# PAGE15.net
KiCad netlist of a schematic drawn in Altium Designer
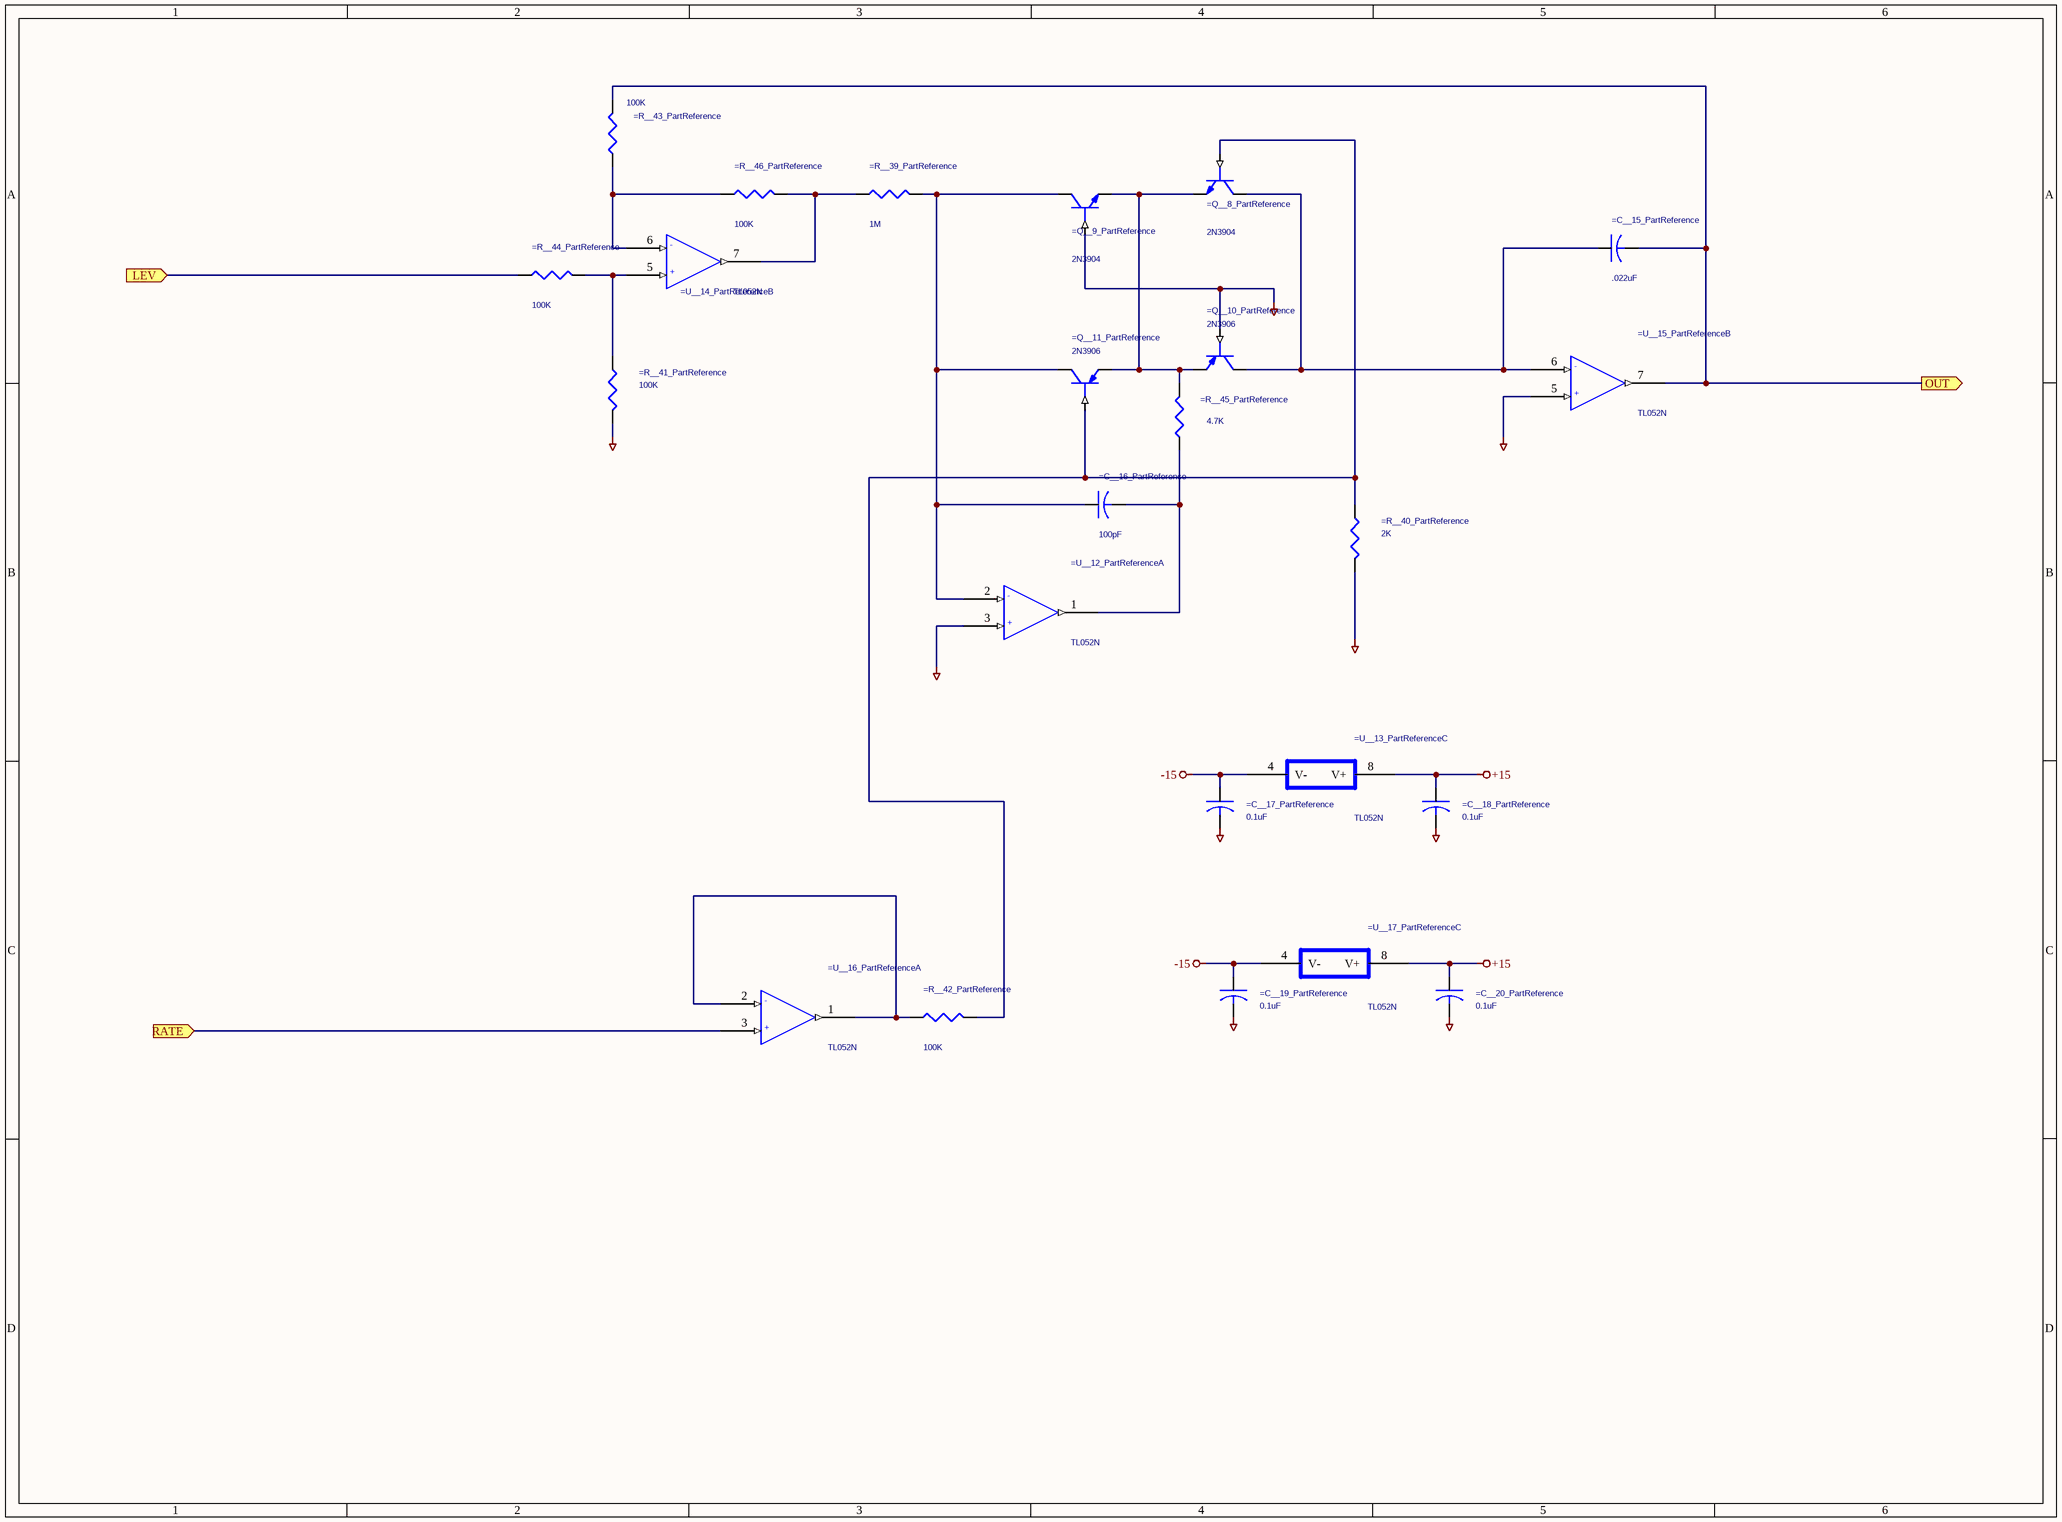
[diagram p0: PAGE15.SchDoc]

(export (version "E")
  (design (tool "Eeschema 10.0.6"))
  (components
    (comp (ref "=C__15_PartReference") (value ".022uF") (libsource (lib "*") (part "CAP_Dup1")))
    (comp (ref "=C__16_PartReference") (value "100pF") (libsource (lib "*") (part "CAP_Dup1")))
    (comp (ref "=C__17_PartReference") (value "0.1uF") (libsource (lib "*") (part "CAP_Dup1")))
    (comp (ref "=C__18_PartReference") (value "0.1uF") (libsource (lib "*") (part "CAP_Dup1")))
    (comp (ref "=C__19_PartReference") (value "0.1uF") (libsource (lib "*") (part "CAP_Dup1")))
    (comp (ref "=C__20_PartReference") (value "0.1uF") (libsource (lib "*") (part "CAP_Dup1")))
    (comp (ref "=Q__8_PartReference") (value "2N3904") (footprint "TO92") (libsource (lib "*") (part "NPN")))
    (comp (ref "=Q__9_PartReference") (value "2N3904") (footprint "TO92") (libsource (lib "*") (part "NPN")))
    (comp (ref "=Q__10_PartReference") (value "2N3906") (footprint "TO92") (libsource (lib "*") (part "PNP")))
    (comp (ref "=Q__11_PartReference") (value "2N3906") (footprint "TO92") (libsource (lib "*") (part "PNP")))
    (comp (ref "=R__39_PartReference") (value "1M") (libsource (lib "*") (part "R_Dup1")))
    (comp (ref "=R__40_PartReference") (value "2K") (libsource (lib "*") (part "R_Dup1")))
    (comp (ref "=R__41_PartReference") (value "100K") (libsource (lib "*") (part "R_Dup1")))
    (comp (ref "=R__42_PartReference") (value "100K") (libsource (lib "*") (part "R_Dup1")))
    (comp (ref "=R__43_PartReference") (value "100K") (libsource (lib "*") (part "R_Dup1")))
    (comp (ref "=R__44_PartReference") (value "100K") (libsource (lib "*") (part "R_Dup1")))
    (comp (ref "=R__45_PartReference") (value "4.7K") (libsource (lib "*") (part "R_Dup1")))
    (comp (ref "=R__46_PartReference") (value "100K") (libsource (lib "*") (part "R_Dup1")))
    (comp (ref "=U__12_PartReference")
      (value "TL052N")
      (footprint "DIP8")
      (libsource (lib "*") (part "TL052N"))
    )
    (comp (ref "=U__13_PartReference")
      (value "TL052N")
      (footprint "DIP8")
      (libsource (lib "*") (part "TL052N"))
    )
    (comp (ref "=U__14_PartReference")
      (value "TL052N")
      (footprint "DIP8")
      (libsource (lib "*") (part "TL052N"))
    )
    (comp (ref "=U__15_PartReference")
      (value "TL052N")
      (footprint "DIP8")
      (libsource (lib "*") (part "TL052N"))
    )
    (comp (ref "=U__16_PartReference")
      (value "TL052N")
      (footprint "DIP8")
      (libsource (lib "*") (part "TL052N"))
    )
    (comp (ref "=U__17_PartReference")
      (value "TL052N")
      (footprint "DIP8")
      (libsource (lib "*") (part "TL052N"))
    )
  )
  (nets
    (net (code "1") (name "+15") (class "Default")
      (node (ref "=C__18_PartReference") (pin "1") (pinfunction "1_1") (pintype "passive"))
      (node (ref "=C__20_PartReference") (pin "1") (pinfunction "1_1") (pintype "passive"))
      (node (ref "=U__13_PartReference") (pin "8") (pinfunction "V+_8") (pintype "passive"))
      (node (ref "=U__17_PartReference") (pin "8") (pinfunction "V+_8") (pintype "passive"))
    )
    (net (code "2") (name "-15") (class "Default")
      (node (ref "=C__17_PartReference") (pin "1") (pinfunction "1_1") (pintype "passive"))
      (node (ref "=C__19_PartReference") (pin "1") (pinfunction "1_1") (pintype "passive"))
      (node (ref "=U__13_PartReference") (pin "4") (pinfunction "V-_4") (pintype "passive"))
      (node (ref "=U__17_PartReference") (pin "4") (pinfunction "V-_4") (pintype "passive"))
    )
    (net (code "3") (name "/LEV") (class "Default")
      (node (ref "=R__44_PartReference") (pin "1") (pinfunction "1_1") (pintype "passive"))
    )
    (net (code "4") (name "/OUT") (class "Default")
      (node (ref "=C__15_PartReference") (pin "2") (pinfunction "2_2") (pintype "passive"))
      (node (ref "=R__43_PartReference") (pin "2") (pinfunction "2_2") (pintype "passive"))
      (node (ref "=U__15_PartReference") (pin "7") (pinfunction "OUT_7") (pintype "output"))
    )
    (net (code "5") (name "/RATE") (class "Default")
      (node (ref "=U__16_PartReference") (pin "3") (pinfunction "+_3") (pintype "input"))
    )
    (net (code "6") (name "AGND") (class "Default")
      (node (ref "=C__17_PartReference") (pin "2") (pinfunction "2_2") (pintype "passive"))
      (node (ref "=C__18_PartReference") (pin "2") (pinfunction "2_2") (pintype "passive"))
      (node (ref "=C__19_PartReference") (pin "2") (pinfunction "2_2") (pintype "passive"))
      (node (ref "=C__20_PartReference") (pin "2") (pinfunction "2_2") (pintype "passive"))
      (node (ref "=Q__10_PartReference") (pin "BASE") (pinfunction "BASE_BASE") (pintype "input"))
      (node (ref "=Q__9_PartReference") (pin "BASE") (pinfunction "BASE_BASE") (pintype "input"))
      (node (ref "=R__40_PartReference") (pin "2") (pinfunction "2_2") (pintype "passive"))
      (node (ref "=R__41_PartReference") (pin "2") (pinfunction "2_2") (pintype "passive"))
      (node (ref "=U__12_PartReference") (pin "3") (pinfunction "+_3") (pintype "input"))
      (node (ref "=U__15_PartReference") (pin "5") (pinfunction "+_5") (pintype "input"))
    )
    (net (code "7") (name "Net-(=Q__10_PartReference-PadEMITTER)") (class "Default")
      (node (ref "=Q__10_PartReference") (pin "EMITTER") (pinfunction "EMITTER_EMITTER") (pintype "passive"))
      (node (ref "=Q__11_PartReference") (pin "EMITTER") (pinfunction "EMITTER_EMITTER") (pintype "passive"))
      (node (ref "=Q__8_PartReference") (pin "EMITTER") (pinfunction "EMITTER_EMITTER") (pintype "passive"))
      (node (ref "=Q__9_PartReference") (pin "EMITTER") (pinfunction "EMITTER_EMITTER") (pintype "passive"))
      (node (ref "=R__45_PartReference") (pin "2") (pinfunction "2_2") (pintype "passive"))
    )
    (net (code "8") (name "Net-(=Q__11_PartReference-PadBASE)") (class "Default")
      (node (ref "=Q__11_PartReference") (pin "BASE") (pinfunction "BASE_BASE") (pintype "input"))
      (node (ref "=Q__8_PartReference") (pin "BASE") (pinfunction "BASE_BASE") (pintype "input"))
      (node (ref "=R__40_PartReference") (pin "1") (pinfunction "1_1") (pintype "passive"))
      (node (ref "=R__42_PartReference") (pin "2") (pinfunction "2_2") (pintype "passive"))
    )
    (net (code "9") (name "Net-(=U__12_PartReferenceA--)") (class "Default")
      (node (ref "=C__16_PartReference") (pin "1") (pinfunction "1_1") (pintype "passive"))
      (node (ref "=Q__11_PartReference") (pin "COLLECTOR") (pinfunction "COLLECTOR_COLLECTOR") (pintype "passive"))
      (node (ref "=Q__9_PartReference") (pin "COLLECTOR") (pinfunction "COLLECTOR_COLLECTOR") (pintype "passive"))
      (node (ref "=R__39_PartReference") (pin "2") (pinfunction "2_2") (pintype "passive"))
      (node (ref "=U__12_PartReference") (pin "2") (pinfunction "-_2") (pintype "input"))
    )
    (net (code "10") (name "Net-(=U__12_PartReferenceA-OUT)") (class "Default")
      (node (ref "=C__16_PartReference") (pin "2") (pinfunction "2_2") (pintype "passive"))
      (node (ref "=R__45_PartReference") (pin "1") (pinfunction "1_1") (pintype "passive"))
      (node (ref "=U__12_PartReference") (pin "1") (pinfunction "OUT_1") (pintype "output"))
    )
    (net (code "11") (name "Net-(=U__14_PartReferenceB-+)") (class "Default")
      (node (ref "=R__41_PartReference") (pin "1") (pinfunction "1_1") (pintype "passive"))
      (node (ref "=R__44_PartReference") (pin "2") (pinfunction "2_2") (pintype "passive"))
      (node (ref "=U__14_PartReference") (pin "5") (pinfunction "+_5") (pintype "input"))
    )
    (net (code "12") (name "Net-(=U__14_PartReferenceB--)") (class "Default")
      (node (ref "=R__43_PartReference") (pin "1") (pinfunction "1_1") (pintype "passive"))
      (node (ref "=R__46_PartReference") (pin "1") (pinfunction "1_1") (pintype "passive"))
      (node (ref "=U__14_PartReference") (pin "6") (pinfunction "-_6") (pintype "input"))
    )
    (net (code "13") (name "Net-(=U__14_PartReferenceB-OUT)") (class "Default")
      (node (ref "=R__39_PartReference") (pin "1") (pinfunction "1_1") (pintype "passive"))
      (node (ref "=R__46_PartReference") (pin "2") (pinfunction "2_2") (pintype "passive"))
      (node (ref "=U__14_PartReference") (pin "7") (pinfunction "OUT_7") (pintype "output"))
    )
    (net (code "14") (name "Net-(=U__15_PartReferenceB--)") (class "Default")
      (node (ref "=C__15_PartReference") (pin "1") (pinfunction "1_1") (pintype "passive"))
      (node (ref "=Q__10_PartReference") (pin "COLLECTOR") (pinfunction "COLLECTOR_COLLECTOR") (pintype "passive"))
      (node (ref "=Q__8_PartReference") (pin "COLLECTOR") (pinfunction "COLLECTOR_COLLECTOR") (pintype "passive"))
      (node (ref "=U__15_PartReference") (pin "6") (pinfunction "-_6") (pintype "input"))
    )
    (net (code "15") (name "Net-(=U__16_PartReferenceA--)") (class "Default")
      (node (ref "=R__42_PartReference") (pin "1") (pinfunction "1_1") (pintype "passive"))
      (node (ref "=U__16_PartReference") (pin "1") (pinfunction "OUT_1") (pintype "output"))
      (node (ref "=U__16_PartReference") (pin "2") (pinfunction "-_2") (pintype "input"))
    )
  )
)
